# usb-i2c-thingy.net
KiCad netlist of a schematic drawn in EAGLE
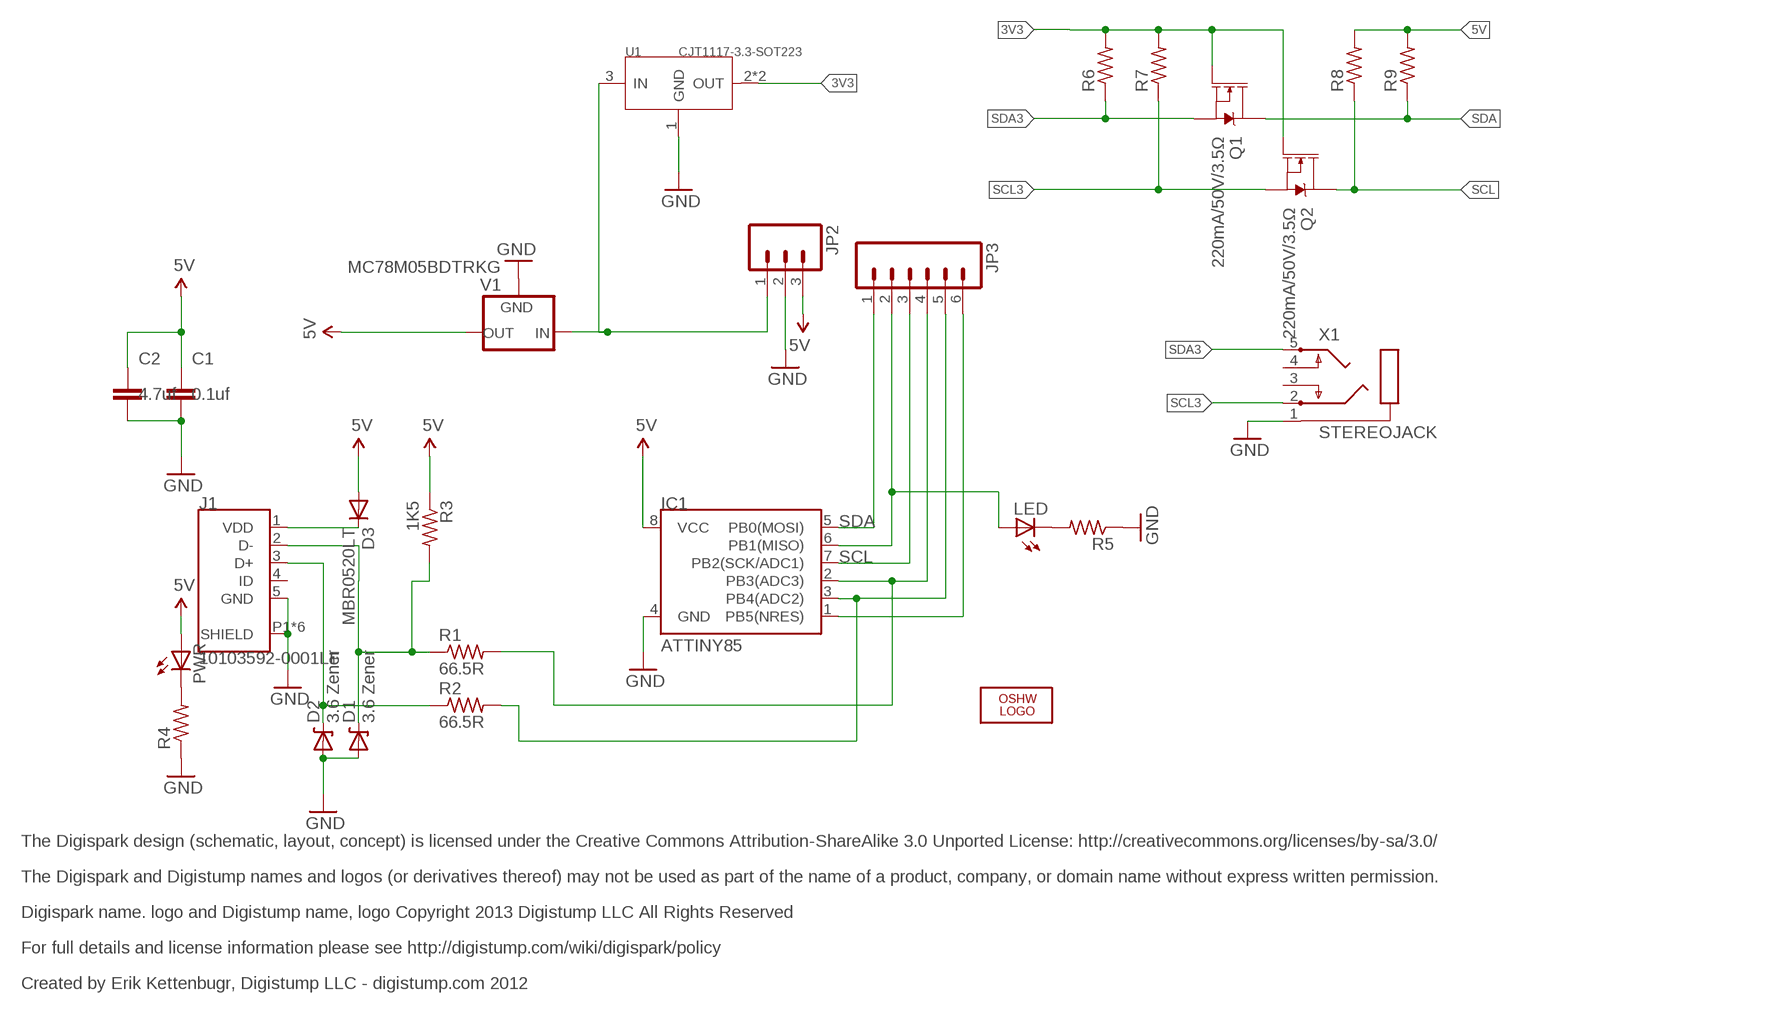
[diagram p0: schematic, sheet 1]

(export (version "E")
  (design (tool "Eeschema 10.0.6"))
  (components
    (comp (ref "C1")
      (value "0.1uf")
      (footprint "eagle-import:C0603")
      (libsource (lib "eagle-import") (part "C-EUC0603"))
    )
    (comp (ref "C2")
      (value "4.7uf")
      (footprint "eagle-import:C0603")
      (libsource (lib "eagle-import") (part "C-EUC0603"))
    )
    (comp (ref "D1")
      (value "3.6 Zener")
      (footprint "eagle-import:SOD-323")
      (libsource (lib "eagle-import") (part "DIODE-ZENER-BZT52"))
    )
    (comp (ref "D2")
      (value "3.6 Zener")
      (footprint "eagle-import:SOD-323")
      (libsource (lib "eagle-import") (part "DIODE-ZENER-BZT52"))
    )
    (comp (ref "D3")
      (value "MBR0520LT")
      (footprint "eagle-import:SOD123")
      (libsource (lib "eagle-import") (part "MBR0520LT"))
    )
    (comp (ref "IC1")
      (value "ATTINY85")
      (footprint "eagle-import:SO08-EIAJ")
      (libsource (lib "eagle-import") (part "ATTINY45"))
    )
    (comp (ref "J1")
      (value "10103592-0001LF")
      (footprint "eagle-import:AMPHENOL_10103592-0001LF")
      (fields (field (name "MF") "Amphenol ICC"))
      (libsource (lib "eagle-import") (part "10103592-0001LF"))
    )
    (comp (ref "JP2")
      (value "M03PTH")
      (footprint "eagle-import:1X03")
      (libsource (lib "eagle-import") (part "M03PTH"))
    )
    (comp (ref "JP3")
      (value "M06SIP")
      (footprint "eagle-import:1X06")
      (libsource (lib "eagle-import") (part "M06SIP"))
    )
    (comp (ref "LED")
      (value "LED0603")
      (footprint "eagle-import:LED-0603")
      (libsource (lib "eagle-import") (part "LED0603"))
    )
    (comp (ref "LOGO2")
      (value "LOGO-OSHW-10MILX0200-NT")
      (footprint "eagle-import:OSHW_10X200_NOTEXT")
      (libsource (lib "eagle-import") (part "LOGO-OSHW-10MILX0200-NT"))
    )
    (comp (ref "PWR")
      (value "LED0603")
      (footprint "eagle-import:LED-0603")
      (libsource (lib "eagle-import") (part "LED0603"))
    )
    (comp (ref "Q1")
      (value "220mA/50V/3.5Ω")
      (footprint "eagle-import:SOT23-3")
      (libsource (lib "eagle-import") (part "MOSFET-NCH-BSS138"))
    )
    (comp (ref "Q2")
      (value "220mA/50V/3.5Ω")
      (footprint "eagle-import:SOT23-3")
      (libsource (lib "eagle-import") (part "MOSFET-NCH-BSS138"))
    )
    (comp (ref "R1")
      (value "66.5R")
      (footprint "eagle-import:R0603")
      (libsource (lib "eagle-import") (part "R-US_R0603"))
    )
    (comp (ref "R2")
      (value "66.5R")
      (footprint "eagle-import:R0603")
      (libsource (lib "eagle-import") (part "R-US_R0603"))
    )
    (comp (ref "R3")
      (value "1K5")
      (footprint "eagle-import:R0603")
      (libsource (lib "eagle-import") (part "R-US_R0603"))
    )
    (comp (ref "R4")
      (value "R-US_R0603")
      (footprint "eagle-import:R0603")
      (libsource (lib "eagle-import") (part "R-US_R0603"))
    )
    (comp (ref "R5")
      (value "R-US_R0603")
      (footprint "eagle-import:R0603")
      (libsource (lib "eagle-import") (part "R-US_R0603"))
    )
    (comp (ref "R6")
      (value "R-US_R0603")
      (footprint "eagle-import:R0603")
      (libsource (lib "eagle-import") (part "R-US_R0603"))
    )
    (comp (ref "R7")
      (value "R-US_R0603")
      (footprint "eagle-import:R0603")
      (libsource (lib "eagle-import") (part "R-US_R0603"))
    )
    (comp (ref "R8")
      (value "R-US_R0603")
      (footprint "eagle-import:R0603")
      (libsource (lib "eagle-import") (part "R-US_R0603"))
    )
    (comp (ref "R9")
      (value "R-US_R0603")
      (footprint "eagle-import:R0603")
      (libsource (lib "eagle-import") (part "R-US_R0603"))
    )
    (comp (ref "U1")
      (value "CJT1117-3.3-SOT223")
      (footprint "eagle-import:SOT-223")
      (fields (field (name "MPN") "CJT1117-3.3"))
      (libsource (lib "eagle-import") (part "PMIC-CJT1117-3.3(SOT223)"))
    )
    (comp (ref "V1")
      (value "MC78M05BDTRKG")
      (footprint "eagle-import:DPACK")
      (libsource (lib "eagle-import") (part "LP2950?CDT-3.0"))
    )
    (comp (ref "X1")
      (value "STEREOJACK")
      (footprint "eagle-import:STX3100")
      (libsource (lib "eagle-import") (part "STEREOJACK"))
    )
  )
  (nets
    (net (code "1") (name "3V3") (class "Default")
      (node (ref "Q1") (pin "1") (pinfunction "G_1") (pintype "bidirectional"))
      (node (ref "Q2") (pin "1") (pinfunction "G_1") (pintype "bidirectional"))
      (node (ref "R6") (pin "2") (pinfunction "2_2") (pintype "passive"))
      (node (ref "R7") (pin "2") (pinfunction "2_2") (pintype "passive"))
      (node (ref "U1") (pin "2") (pinfunction "OUT_2") (pintype "bidirectional"))
      (node (ref "U1") (pin "TER") (pinfunction "OUT_TER") (pintype "bidirectional"))
    )
    (net (code "2") (name "5V") (class "Default")
      (node (ref "C1") (pin "1") (pinfunction "1_1") (pintype "passive"))
      (node (ref "C2") (pin "1") (pinfunction "1_1") (pintype "passive"))
      (node (ref "D3") (pin "A") (pinfunction "A_A") (pintype "passive"))
      (node (ref "IC1") (pin "8") (pinfunction "VCC_8") (pintype "bidirectional"))
      (node (ref "JP2") (pin "3") (pinfunction "3_3") (pintype "passive"))
      (node (ref "PWR") (pin "A") (pinfunction "A_A") (pintype "passive"))
      (node (ref "R3") (pin "1") (pinfunction "1_1") (pintype "passive"))
      (node (ref "R8") (pin "2") (pinfunction "2_2") (pintype "passive"))
      (node (ref "R9") (pin "2") (pinfunction "2_2") (pintype "passive"))
      (node (ref "V1") (pin "3") (pinfunction "OUT_3") (pintype "passive"))
    )
    (net (code "3") (name "GND") (class "Default")
      (node (ref "C1") (pin "2") (pinfunction "2_2") (pintype "passive"))
      (node (ref "C2") (pin "2") (pinfunction "2_2") (pintype "passive"))
      (node (ref "D1") (pin "2") (pinfunction "A_2") (pintype "passive"))
      (node (ref "D2") (pin "2") (pinfunction "A_2") (pintype "passive"))
      (node (ref "IC1") (pin "4") (pinfunction "GND_4") (pintype "bidirectional"))
      (node (ref "J1") (pin "5") (pinfunction "GND_5") (pintype "power_in"))
      (node (ref "J1") (pin "P1") (pinfunction "SHIELD_P1") (pintype "power_in"))
      (node (ref "J1") (pin "P2") (pinfunction "SHIELD_P2") (pintype "power_in"))
      (node (ref "J1") (pin "P3") (pinfunction "SHIELD_P3") (pintype "power_in"))
      (node (ref "J1") (pin "P4") (pinfunction "SHIELD_P4") (pintype "power_in"))
      (node (ref "J1") (pin "P5") (pinfunction "SHIELD_P5") (pintype "power_in"))
      (node (ref "J1") (pin "P6") (pinfunction "SHIELD_P6") (pintype "power_in"))
      (node (ref "JP2") (pin "2") (pinfunction "2_2") (pintype "passive"))
      (node (ref "R4") (pin "1") (pinfunction "1_1") (pintype "passive"))
      (node (ref "R5") (pin "1") (pinfunction "1_1") (pintype "passive"))
      (node (ref "U1") (pin "1") (pinfunction "GND_1") (pintype "bidirectional"))
      (node (ref "V1") (pin "4") (pinfunction "GND_4") (pintype "input"))
      (node (ref "X1") (pin "1") (pinfunction "1_1") (pintype "passive"))
    )
    (net (code "4") (name "Net-(D1-C)") (class "Default")
      (node (ref "D1") (pin "1") (pinfunction "C_1") (pintype "passive"))
      (node (ref "J1") (pin "2") (pinfunction "D-_2") (pintype "bidirectional"))
      (node (ref "R1") (pin "1") (pinfunction "1_1") (pintype "passive"))
      (node (ref "R3") (pin "2") (pinfunction "2_2") (pintype "passive"))
    )
    (net (code "5") (name "Net-(D2-C)") (class "Default")
      (node (ref "D2") (pin "1") (pinfunction "C_1") (pintype "passive"))
      (node (ref "J1") (pin "3") (pinfunction "D+_3") (pintype "bidirectional"))
      (node (ref "R2") (pin "1") (pinfunction "1_1") (pintype "passive"))
    )
    (net (code "6") (name "Net-(IC1-PB1(MISO))") (class "Default")
      (node (ref "IC1") (pin "6") (pinfunction "PB1(MISO)_6") (pintype "bidirectional"))
      (node (ref "JP3") (pin "2") (pinfunction "2_2") (pintype "passive"))
      (node (ref "LED") (pin "A") (pinfunction "A_A") (pintype "passive"))
    )
    (net (code "7") (name "Net-(IC1-PB3(ADC3))") (class "Default")
      (node (ref "IC1") (pin "2") (pinfunction "PB3(ADC3)_2") (pintype "bidirectional"))
      (node (ref "JP3") (pin "4") (pinfunction "4_4") (pintype "passive"))
      (node (ref "R1") (pin "2") (pinfunction "2_2") (pintype "passive"))
    )
    (net (code "8") (name "Net-(IC1-PB4(ADC2))") (class "Default")
      (node (ref "IC1") (pin "3") (pinfunction "PB4(ADC2)_3") (pintype "bidirectional"))
      (node (ref "JP3") (pin "5") (pinfunction "5_5") (pintype "passive"))
      (node (ref "R2") (pin "2") (pinfunction "2_2") (pintype "passive"))
    )
    (net (code "9") (name "Net-(IC1-PB5(NRES))") (class "Default")
      (node (ref "IC1") (pin "1") (pinfunction "PB5(NRES)_1") (pintype "bidirectional"))
      (node (ref "JP3") (pin "6") (pinfunction "6_6") (pintype "passive"))
    )
    (net (code "10") (name "Net-(J1-VDD)") (class "Default")
      (node (ref "D3") (pin "C") (pinfunction "C_C") (pintype "passive"))
      (node (ref "J1") (pin "1") (pinfunction "VDD_1") (pintype "power_in"))
    )
    (net (code "11") (name "Net-(LED-PadC)") (class "Default")
      (node (ref "LED") (pin "C") (pinfunction "C_C") (pintype "passive"))
      (node (ref "R5") (pin "2") (pinfunction "2_2") (pintype "passive"))
    )
    (net (code "12") (name "Net-(PWR-PadC)") (class "Default")
      (node (ref "PWR") (pin "C") (pinfunction "C_C") (pintype "passive"))
      (node (ref "R4") (pin "2") (pinfunction "2_2") (pintype "passive"))
    )
    (net (code "13") (name "Net-(U1-IN)") (class "Default")
      (node (ref "JP2") (pin "1") (pinfunction "1_1") (pintype "passive"))
      (node (ref "U1") (pin "3") (pinfunction "IN_3") (pintype "bidirectional"))
      (node (ref "V1") (pin "1") (pinfunction "IN_1") (pintype "input"))
    )
    (net (code "14") (name "SCL") (class "Default")
      (node (ref "IC1") (pin "7") (pinfunction "PB2(SCK/ADC1)_7") (pintype "bidirectional"))
      (node (ref "JP3") (pin "3") (pinfunction "3_3") (pintype "passive"))
      (node (ref "Q2") (pin "3") (pinfunction "D_3") (pintype "bidirectional"))
      (node (ref "R8") (pin "1") (pinfunction "1_1") (pintype "passive"))
    )
    (net (code "15") (name "SCL3") (class "Default")
      (node (ref "Q2") (pin "2") (pinfunction "S_2") (pintype "bidirectional"))
      (node (ref "R7") (pin "1") (pinfunction "1_1") (pintype "passive"))
      (node (ref "X1") (pin "2") (pinfunction "2_2") (pintype "passive"))
    )
    (net (code "16") (name "SDA") (class "Default")
      (node (ref "IC1") (pin "5") (pinfunction "PB0(MOSI)_5") (pintype "bidirectional"))
      (node (ref "JP3") (pin "1") (pinfunction "1_1") (pintype "passive"))
      (node (ref "Q1") (pin "3") (pinfunction "D_3") (pintype "bidirectional"))
      (node (ref "R9") (pin "1") (pinfunction "1_1") (pintype "passive"))
    )
    (net (code "17") (name "SDA3") (class "Default")
      (node (ref "Q1") (pin "2") (pinfunction "S_2") (pintype "bidirectional"))
      (node (ref "R6") (pin "1") (pinfunction "1_1") (pintype "passive"))
      (node (ref "X1") (pin "5") (pinfunction "5_5") (pintype "passive"))
    )
    (net (code "18") (name "unconnected-(J1-ID-Pad4)") (class "Default")
      (node (ref "J1") (pin "4") (pinfunction "ID_4") (pintype "bidirectional"))
    )
    (net (code "19") (name "unconnected-(X1-Pad3)") (class "Default")
      (node (ref "X1") (pin "3") (pinfunction "3_3") (pintype "passive"))
    )
    (net (code "20") (name "unconnected-(X1-Pad4)") (class "Default")
      (node (ref "X1") (pin "4") (pinfunction "4_4") (pintype "passive"))
    )
  )
)
